# CH32V203_Wireless_Charge_V1_1.net
KiCad netlist of a schematic drawn in EasyEDA Pro
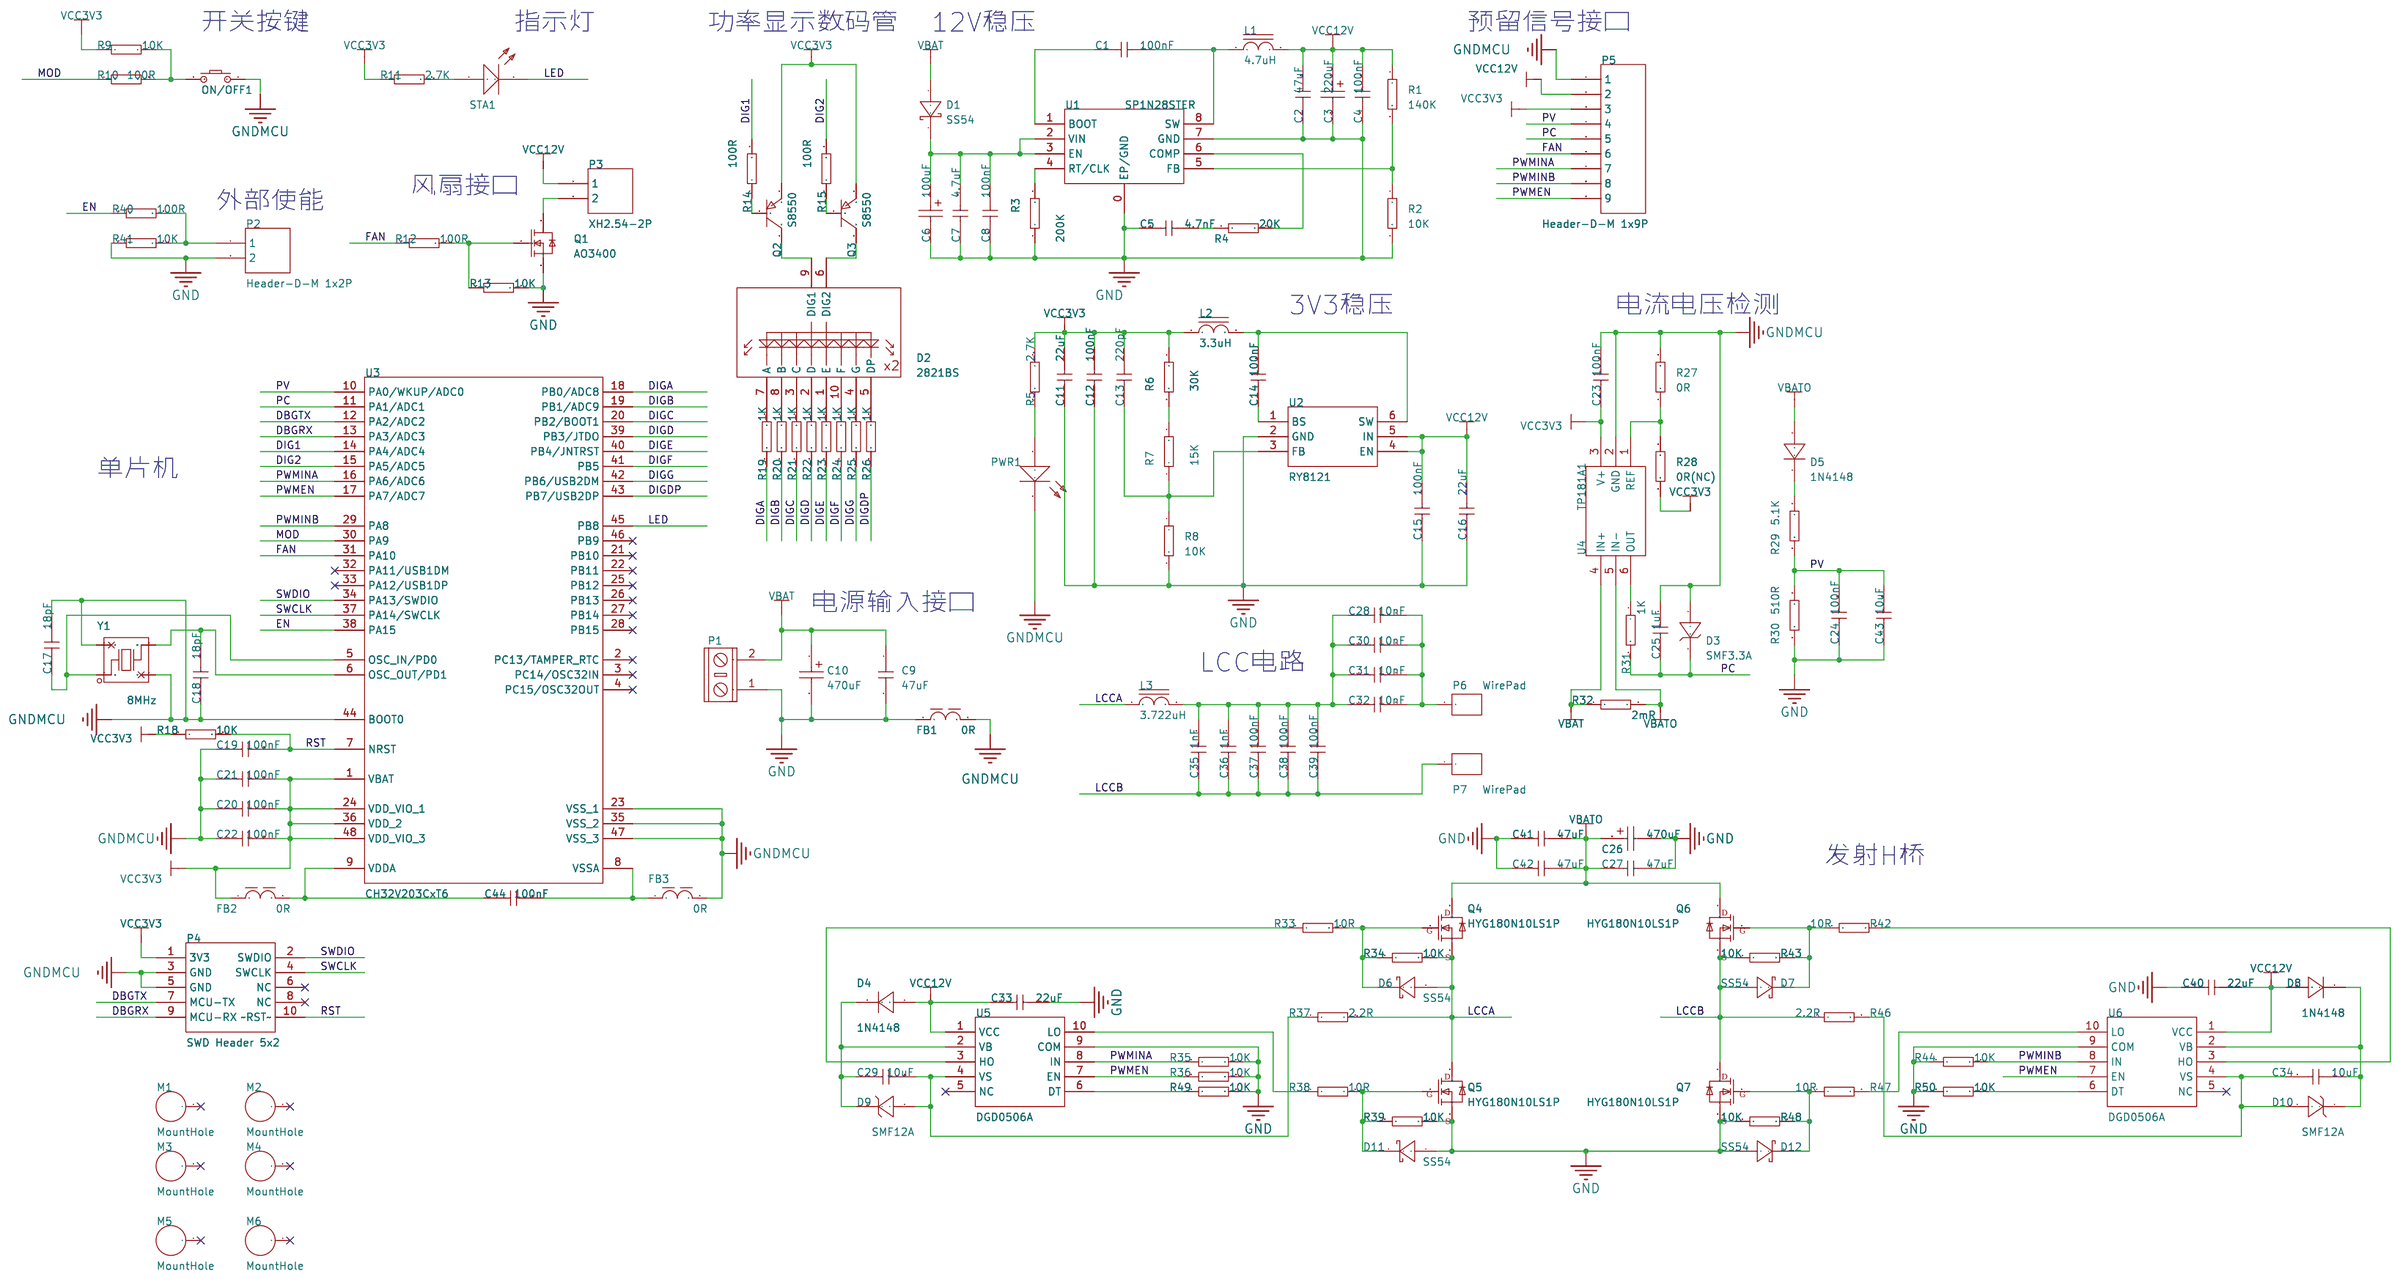
[diagram p0: schematic sheet]

(export (version "E")
  (design (tool "Eeschema 10.0.6"))
  (components
    (comp (ref "C1")
      (value "100nF")
      (footprint "easyedapro:CAPC1608[0603]S-N")
      (libsource (lib "easyedapro") (part "100nF 0603 50V X7R"))
    )
    (comp (ref "C2")
      (value "47uF")
      (footprint "easyedapro:CAPC3216[1206]S")
      (libsource (lib "easyedapro") (part "47uF 1206 25V X5R"))
    )
    (comp (ref "C3")
      (value "220uF")
      (footprint "easyedapro:Cap-S-D 2.5-6.3X8")
      (libsource (lib "easyedapro") (part "S-D 220uF 25V 6.3x8"))
    )
    (comp (ref "C4")
      (value "100nF")
      (footprint "easyedapro:CAPC1608[0603]S-N")
      (libsource (lib "easyedapro") (part "100nF 0603 50V X7R"))
    )
    (comp (ref "C5")
      (value "4.7nF")
      (footprint "easyedapro:CAPC1608[0603]S-N")
      (libsource (lib "easyedapro") (part "4.7nF 0603 50V X7R"))
    )
    (comp (ref "C6")
      (value "100uF")
      (footprint "easyedapro:Cap-S-D 2.5-6.3X8")
      (libsource (lib "easyedapro") (part "S-D 100uF 35V 6.3x8"))
    )
    (comp (ref "C7")
      (value "4.7uF")
      (footprint "easyedapro:CAPC3216[1206]S")
      (libsource (lib "easyedapro") (part "4.7uF 1206 35V X5R"))
    )
    (comp (ref "C8")
      (value "100nF")
      (footprint "easyedapro:CAPC1608[0603]S-N")
      (libsource (lib "easyedapro") (part "100nF 0603 50V X7R"))
    )
    (comp (ref "C9")
      (value "47uF")
      (footprint "easyedapro:CAPC4532[1812]S")
      (libsource (lib "easyedapro") (part "47uF 1812 50V X5R"))
    )
    (comp (ref "C10")
      (value "470uF")
      (footprint "easyedapro:Cap-S-D 3.5-8x14")
      (libsource (lib "easyedapro") (part "S-D 470uF 35V 8x14"))
    )
    (comp (ref "C11")
      (value "22uF")
      (footprint "easyedapro:CAPC2012[0805]S-N")
      (libsource (lib "easyedapro") (part "22uF 0805 25V X5R"))
    )
    (comp (ref "C12")
      (value "100nF")
      (footprint "easyedapro:CAPC1608[0603]S-N")
      (libsource (lib "easyedapro") (part "100nF 0603 50V X7R"))
    )
    (comp (ref "C13")
      (value "220pF")
      (footprint "easyedapro:CAPC1608[0603]S-N")
      (libsource (lib "easyedapro") (part "220pF 0603 50V X7R"))
    )
    (comp (ref "C14")
      (value "100nF")
      (footprint "easyedapro:CAPC1608[0603]S-N")
      (libsource (lib "easyedapro") (part "100nF 0603 50V X7R"))
    )
    (comp (ref "C15")
      (value "100nF")
      (footprint "easyedapro:CAPC1608[0603]S-N")
      (libsource (lib "easyedapro") (part "100nF 0603 50V X7R"))
    )
    (comp (ref "C16")
      (value "22uF")
      (footprint "easyedapro:CAPC2012[0805]S-N")
      (libsource (lib "easyedapro") (part "22uF 0805 25V X5R"))
    )
    (comp (ref "C17")
      (value "18pF")
      (footprint "easyedapro:CAPC1608[0603]S-N")
      (libsource (lib "easyedapro") (part "18pF 0603 50V COG"))
    )
    (comp (ref "C18")
      (value "18pF")
      (footprint "easyedapro:CAPC1608[0603]S-N")
      (libsource (lib "easyedapro") (part "18pF 0603 50V COG"))
    )
    (comp (ref "C19")
      (value "100nF")
      (footprint "easyedapro:CAPC1608[0603]S-N")
      (libsource (lib "easyedapro") (part "100nF 0603 50V X7R"))
    )
    (comp (ref "C20")
      (value "100nF")
      (footprint "easyedapro:CAPC1608[0603]S-N")
      (libsource (lib "easyedapro") (part "100nF 0603 50V X7R"))
    )
    (comp (ref "C21")
      (value "100nF")
      (footprint "easyedapro:CAPC1608[0603]S-N")
      (libsource (lib "easyedapro") (part "100nF 0603 50V X7R"))
    )
    (comp (ref "C22")
      (value "100nF")
      (footprint "easyedapro:CAPC1608[0603]S-N")
      (libsource (lib "easyedapro") (part "100nF 0603 50V X7R"))
    )
    (comp (ref "C23")
      (value "100nF")
      (footprint "easyedapro:CAPC1608[0603]S-N")
      (libsource (lib "easyedapro") (part "100nF 0603 50V X7R"))
    )
    (comp (ref "C24")
      (value "100nF")
      (footprint "easyedapro:CAPC1608[0603]S-N")
      (libsource (lib "easyedapro") (part "100nF 0603 50V X7R"))
    )
    (comp (ref "C25")
      (value "1uF")
      (footprint "easyedapro:CAPC1608[0603]S-N")
      (libsource (lib "easyedapro") (part "1uF 0603 16V X7R"))
    )
    (comp (ref "C26")
      (value "470uF")
      (footprint "easyedapro:Cap-S-D 3.5-8x14")
      (libsource (lib "easyedapro") (part "S-D 470uF 35V 8x14"))
    )
    (comp (ref "C27")
      (value "47uF")
      (footprint "easyedapro:CAPC4532[1812]S")
      (libsource (lib "easyedapro") (part "47uF 1812 50V X5R"))
    )
    (comp (ref "C28")
      (value "10nF")
      (footprint "easyedapro:CAPC3216[1206]S")
      (libsource (lib "easyedapro") (part "10nF 1206 100V C0G"))
    )
    (comp (ref "C29")
      (value "10uF")
      (footprint "easyedapro:CAPC2012[0805]S-N")
      (libsource (lib "easyedapro") (part "10uF 0805 25V X5R"))
    )
    (comp (ref "C30")
      (value "10nF")
      (footprint "easyedapro:CAPC3216[1206]S")
      (libsource (lib "easyedapro") (part "10nF 1206 100V C0G"))
    )
    (comp (ref "C31")
      (value "10nF")
      (footprint "easyedapro:CAPC3216[1206]S")
      (libsource (lib "easyedapro") (part "10nF 1206 100V C0G"))
    )
    (comp (ref "C32")
      (value "10nF")
      (footprint "easyedapro:CAPC3216[1206]S")
      (libsource (lib "easyedapro") (part "10nF 1206 100V C0G"))
    )
    (comp (ref "C33")
      (value "22uF")
      (footprint "easyedapro:CAPC2012[0805]S-N")
      (libsource (lib "easyedapro") (part "22uF 0805 25V X5R"))
    )
    (comp (ref "C34")
      (value "10uF")
      (footprint "easyedapro:CAPC2012[0805]S-N")
      (libsource (lib "easyedapro") (part "10uF 0805 25V X5R"))
    )
    (comp (ref "C35")
      (value "1nF")
      (footprint "easyedapro:CAPC3216[1206]S")
      (libsource (lib "easyedapro") (part "1nF 1206 100V C0G"))
    )
    (comp (ref "C36")
      (value "1nF")
      (footprint "easyedapro:CAPC3216[1206]S")
      (libsource (lib "easyedapro") (part "1nF 1206 100V C0G"))
    )
    (comp (ref "C37")
      (value "100nF")
      (footprint "easyedapro:CAPC3216[1206]S")
      (libsource (lib "easyedapro") (part "100nF 1206 100V C0G"))
    )
    (comp (ref "C38")
      (value "100nF")
      (footprint "easyedapro:CAPC3216[1206]S")
      (libsource (lib "easyedapro") (part "100nF 1206 100V C0G"))
    )
    (comp (ref "C39")
      (value "100nF")
      (footprint "easyedapro:CAPC3216[1206]S")
      (libsource (lib "easyedapro") (part "100nF 1206 100V C0G"))
    )
    (comp (ref "C40")
      (value "22uF")
      (footprint "easyedapro:CAPC2012[0805]S-N")
      (libsource (lib "easyedapro") (part "22uF 0805 25V X5R"))
    )
    (comp (ref "C41")
      (value "47uF")
      (footprint "easyedapro:CAPC4532[1812]S")
      (libsource (lib "easyedapro") (part "47uF 1812 50V X5R"))
    )
    (comp (ref "C42")
      (value "47uF")
      (footprint "easyedapro:CAPC4532[1812]S")
      (libsource (lib "easyedapro") (part "47uF 1812 50V X5R"))
    )
    (comp (ref "C43")
      (value "10uF")
      (footprint "easyedapro:CAPC2012[0805]S-N")
      (libsource (lib "easyedapro") (part "10uF 0805 25V X5R"))
    )
    (comp (ref "C44")
      (value "100nF")
      (footprint "easyedapro:CAPC1608[0603]S-N")
      (libsource (lib "easyedapro") (part "100nF 0603 50V X7R"))
    )
    (comp (ref "D1")
      (value "SS54")
      (footprint "easyedapro:SMA-L[DO-214AC]")
      (libsource (lib "easyedapro") (part "SS54"))
    )
    (comp (ref "D2")
      (value "2821BS")
      (footprint "easyedapro:2821AS/BS")
      (libsource (lib "easyedapro") (part "2821BS"))
    )
    (comp (ref "D3")
      (value "SMF3.3A")
      (footprint "easyedapro:SOD-123-L")
      (libsource (lib "easyedapro") (part "Diode TVS Uni-Dir_1"))
    )
    (comp (ref "D4")
      (value "1N4148")
      (footprint "easyedapro:SOD-123-L")
      (libsource (lib "easyedapro") (part "Diode"))
    )
    (comp (ref "D5")
      (value "1N4148")
      (footprint "easyedapro:SOD-123-L")
      (libsource (lib "easyedapro") (part "Diode"))
    )
    (comp (ref "D6")
      (value "SS54")
      (footprint "easyedapro:SMA-L[DO-214AC]")
      (libsource (lib "easyedapro") (part "SS54"))
    )
    (comp (ref "D7")
      (value "SS54")
      (footprint "easyedapro:SMA-L[DO-214AC]")
      (libsource (lib "easyedapro") (part "SS54"))
    )
    (comp (ref "D8")
      (value "1N4148")
      (footprint "easyedapro:SOD-123-L")
      (libsource (lib "easyedapro") (part "Diode"))
    )
    (comp (ref "D9")
      (value "SMF12A")
      (footprint "easyedapro:SOD-123-L")
      (libsource (lib "easyedapro") (part "Diode TVS Uni-Dir"))
    )
    (comp (ref "D10")
      (value "SMF12A")
      (footprint "easyedapro:SOD-123-L")
      (libsource (lib "easyedapro") (part "Diode TVS Uni-Dir"))
    )
    (comp (ref "D11")
      (value "SS54")
      (footprint "easyedapro:SMA-L[DO-214AC]")
      (libsource (lib "easyedapro") (part "SS54"))
    )
    (comp (ref "D12")
      (value "SS54")
      (footprint "easyedapro:SMA-L[DO-214AC]")
      (libsource (lib "easyedapro") (part "SS54"))
    )
    (comp (ref "FB1")
      (value "0R")
      (footprint "easyedapro:INDC1608[0603]S")
      (libsource (lib "easyedapro") (part "FB-Chip"))
    )
    (comp (ref "FB2")
      (value "0R")
      (footprint "easyedapro:INDC1608[0603]S")
      (libsource (lib "easyedapro") (part "FB-Chip"))
    )
    (comp (ref "FB3")
      (value "0R")
      (footprint "easyedapro:INDC1608[0603]S")
      (libsource (lib "easyedapro") (part "FB-Chip"))
    )
    (comp (ref "L1")
      (value "4.7uH")
      (footprint "easyedapro:0630 TPC 7*7*3")
      (libsource (lib "easyedapro") (part "Ind-Power"))
    )
    (comp (ref "L2")
      (value "3.3uH")
      (footprint "easyedapro:0402 TPC 4*4*2")
      (libsource (lib "easyedapro") (part "Ind-Power_1"))
    )
    (comp (ref "L3")
      (value "3.722uH")
      (footprint "easyedapro:T94/106-LAY")
      (libsource (lib "easyedapro") (part "Ind-Power_2"))
    )
    (comp (ref "M1")
      (value "MountHole")
      (footprint "easyedapro:M3-MountHole-Plated")
      (libsource (lib "easyedapro") (part "MountHole"))
    )
    (comp (ref "M2")
      (value "MountHole")
      (footprint "easyedapro:M3-MountHole-Plated")
      (libsource (lib "easyedapro") (part "MountHole"))
    )
    (comp (ref "M3")
      (value "MountHole")
      (footprint "easyedapro:M3-MountHole-Plated")
      (libsource (lib "easyedapro") (part "MountHole"))
    )
    (comp (ref "M4")
      (value "MountHole")
      (footprint "easyedapro:M3-MountHole-Plated")
      (libsource (lib "easyedapro") (part "MountHole"))
    )
    (comp (ref "M5")
      (value "MountHole")
      (footprint "easyedapro:M3-MountHole-Plated")
      (libsource (lib "easyedapro") (part "MountHole"))
    )
    (comp (ref "M6")
      (value "MountHole")
      (footprint "easyedapro:M3-MountHole-Plated")
      (libsource (lib "easyedapro") (part "MountHole"))
    )
    (comp (ref "ON/OFF1")
      (value "Button")
      (footprint "easyedapro:KEY-2-DIP-6*6-S")
      (libsource (lib "easyedapro") (part "KEY"))
    )
    (comp (ref "P1")
      (value "KF/WJ/DG 30x connecter")
      (footprint "easyedapro:KF/WJ/DG 301-2p-5.0mm")
      (libsource (lib "easyedapro") (part "KF/WJ/DG 30x"))
    )
    (comp (ref "P2")
      (value "Header-D-M 1x2P")
      (footprint "easyedapro:HDR1X2-M")
      (libsource (lib "easyedapro") (part "Header-D-M 1x2P"))
    )
    (comp (ref "P3")
      (value "XH2.54-2P")
      (footprint "easyedapro:XH2.54-2P-DV")
      (libsource (lib "easyedapro") (part "XH2.54-2P"))
    )
    (comp (ref "P4")
      (value "SWD Header 5x2")
      (footprint "easyedapro:HDR2X5-M")
      (libsource (lib "easyedapro") (part "SWD Header 5x2"))
    )
    (comp (ref "P5")
      (value "Header-D-M 1x9P")
      (footprint "easyedapro:HDR1X9-M")
      (libsource (lib "easyedapro") (part "Header-D-M 1x9P"))
    )
    (comp (ref "P6")
      (value "WirePad")
      (footprint "easyedapro:WirePad-4x6")
      (libsource (lib "easyedapro") (part "WirePad"))
    )
    (comp (ref "P7")
      (value "WirePad")
      (footprint "easyedapro:WirePad-4x6")
      (libsource (lib "easyedapro") (part "WirePad"))
    )
    (comp (ref "PWR1")
      (value "LED 3R")
      (footprint "easyedapro:LED-R3-H5-SINGLE-R")
      (libsource (lib "easyedapro") (part "LED DIP Red"))
    )
    (comp (ref "Q1")
      (value "AO3400")
      (footprint "easyedapro:SOT-23")
      (libsource (lib "easyedapro") (part "AO3400"))
    )
    (comp (ref "Q2")
      (value "S8550")
      (footprint "easyedapro:SOT-23")
      (libsource (lib "easyedapro") (part "PNP S8550"))
    )
    (comp (ref "Q3")
      (value "S8550")
      (footprint "easyedapro:SOT-23")
      (libsource (lib "easyedapro") (part "PNP S8550"))
    )
    (comp (ref "Q4")
      (value "HYG180N10LS1P")
      (footprint "easyedapro:TO-220-LAY")
      (libsource (lib "easyedapro") (part "HYG180N10LS1P"))
    )
    (comp (ref "Q5")
      (value "HYG180N10LS1P")
      (footprint "easyedapro:TO-220-LAY")
      (libsource (lib "easyedapro") (part "HYG180N10LS1P"))
    )
    (comp (ref "Q6")
      (value "HYG180N10LS1P")
      (footprint "easyedapro:TO-220-LAY")
      (libsource (lib "easyedapro") (part "HYG180N10LS1P"))
    )
    (comp (ref "Q7")
      (value "HYG180N10LS1P")
      (footprint "easyedapro:TO-220-LAY")
      (libsource (lib "easyedapro") (part "HYG180N10LS1P"))
    )
    (comp (ref "R1")
      (value "140K")
      (footprint "easyedapro:RESC1608[0603]S-N")
      (libsource (lib "easyedapro") (part "Res-Chip_6"))
    )
    (comp (ref "R2")
      (value "10K")
      (footprint "easyedapro:RESC1608[0603]S-N")
      (libsource (lib "easyedapro") (part "Res-Chip"))
    )
    (comp (ref "R3")
      (value "200K")
      (footprint "easyedapro:RESC1608[0603]S-N")
      (libsource (lib "easyedapro") (part "Res-Chip_4"))
    )
    (comp (ref "R4")
      (value "20K")
      (footprint "easyedapro:RESC1608[0603]S-N")
      (libsource (lib "easyedapro") (part "Res-Chip_5"))
    )
    (comp (ref "R5")
      (value "2.7K")
      (footprint "easyedapro:RESC1608[0603]S-N")
      (libsource (lib "easyedapro") (part "Res-Chip_3"))
    )
    (comp (ref "R6")
      (value "30K")
      (footprint "easyedapro:RESC1608[0603]S-N")
      (libsource (lib "easyedapro") (part "Res-Chip_8"))
    )
    (comp (ref "R7")
      (value "15K")
      (footprint "easyedapro:RESC1608[0603]S-N")
      (libsource (lib "easyedapro") (part "Res-Chip_7"))
    )
    (comp (ref "R8")
      (value "10K")
      (footprint "easyedapro:RESC1608[0603]S-N")
      (libsource (lib "easyedapro") (part "Res-Chip"))
    )
    (comp (ref "R9")
      (value "10K")
      (footprint "easyedapro:RESC1608[0603]S-N")
      (libsource (lib "easyedapro") (part "Res-Chip"))
    )
    (comp (ref "R10")
      (value "100R")
      (footprint "easyedapro:RESC1608[0603]S-N")
      (libsource (lib "easyedapro") (part "Res-Chip_1"))
    )
    (comp (ref "R11")
      (value "2.7K")
      (footprint "easyedapro:RESC1608[0603]S-N")
      (libsource (lib "easyedapro") (part "Res-Chip_3"))
    )
    (comp (ref "R12")
      (value "100R")
      (footprint "easyedapro:RESC1608[0603]S-N")
      (libsource (lib "easyedapro") (part "Res-Chip_1"))
    )
    (comp (ref "R13")
      (value "10K")
      (footprint "easyedapro:RESC1608[0603]S-N")
      (libsource (lib "easyedapro") (part "Res-Chip"))
    )
    (comp (ref "R14")
      (value "100R")
      (footprint "easyedapro:RESC1608[0603]S-N")
      (libsource (lib "easyedapro") (part "Res-Chip_1"))
    )
    (comp (ref "R15")
      (value "100R")
      (footprint "easyedapro:RESC1608[0603]S-N")
      (libsource (lib "easyedapro") (part "Res-Chip_1"))
    )
    (comp (ref "R18")
      (value "10K")
      (footprint "easyedapro:RESC1608[0603]S-N")
      (libsource (lib "easyedapro") (part "Res-Chip"))
    )
    (comp (ref "R19")
      (value "1K")
      (footprint "easyedapro:RESC1608[0603]S-N")
      (libsource (lib "easyedapro") (part "Res-Chip_2"))
    )
    (comp (ref "R20")
      (value "1K")
      (footprint "easyedapro:RESC1608[0603]S-N")
      (libsource (lib "easyedapro") (part "Res-Chip_2"))
    )
    (comp (ref "R21")
      (value "1K")
      (footprint "easyedapro:RESC1608[0603]S-N")
      (libsource (lib "easyedapro") (part "Res-Chip_2"))
    )
    (comp (ref "R22")
      (value "1K")
      (footprint "easyedapro:RESC1608[0603]S-N")
      (libsource (lib "easyedapro") (part "Res-Chip_2"))
    )
    (comp (ref "R23")
      (value "1K")
      (footprint "easyedapro:RESC1608[0603]S-N")
      (libsource (lib "easyedapro") (part "Res-Chip_2"))
    )
    (comp (ref "R24")
      (value "1K")
      (footprint "easyedapro:RESC1608[0603]S-N")
      (libsource (lib "easyedapro") (part "Res-Chip_2"))
    )
    (comp (ref "R25")
      (value "1K")
      (footprint "easyedapro:RESC1608[0603]S-N")
      (libsource (lib "easyedapro") (part "Res-Chip_2"))
    )
    (comp (ref "R26")
      (value "1K")
      (footprint "easyedapro:RESC1608[0603]S-N")
      (libsource (lib "easyedapro") (part "Res-Chip_2"))
    )
    (comp (ref "R27")
      (value "0R")
      (footprint "easyedapro:RESC1608[0603]S-N")
      (libsource (lib "easyedapro") (part "Res-Chip_12"))
    )
    (comp (ref "R28")
      (value "0R(NC)")
      (footprint "easyedapro:RESC1608[0603]S-N")
      (libsource (lib "easyedapro") (part "Res-Chip_11"))
    )
    (comp (ref "R29")
      (value "5.1K")
      (footprint "easyedapro:RESC1608[0603]S-N")
      (libsource (lib "easyedapro") (part "Res-Chip_14"))
    )
    (comp (ref "R30")
      (value "510R")
      (footprint "easyedapro:RESC1608[0603]S-N")
      (libsource (lib "easyedapro") (part "Res-Chip_15"))
    )
    (comp (ref "R31")
      (value "1K")
      (footprint "easyedapro:RESC1608[0603]S-N")
      (libsource (lib "easyedapro") (part "Res-Chip_2"))
    )
    (comp (ref "R32")
      (value "2mR")
      (footprint "easyedapro:RESC6332[2512]S")
      (libsource (lib "easyedapro") (part "Res-Chip_10"))
    )
    (comp (ref "R33")
      (value "10R")
      (footprint "easyedapro:RESC2012[0805]S-N")
      (libsource (lib "easyedapro") (part "Res-Chip_9"))
    )
    (comp (ref "R34")
      (value "10K")
      (footprint "easyedapro:RESC1608[0603]S-N")
      (libsource (lib "easyedapro") (part "Res-Chip"))
    )
    (comp (ref "R35")
      (value "10K")
      (footprint "easyedapro:RESC1608[0603]S-N")
      (libsource (lib "easyedapro") (part "Res-Chip"))
    )
    (comp (ref "R36")
      (value "10K")
      (footprint "easyedapro:RESC1608[0603]S-N")
      (libsource (lib "easyedapro") (part "Res-Chip"))
    )
    (comp (ref "R37")
      (value "2.2R")
      (footprint "easyedapro:RESC2012[0805]S-N")
      (libsource (lib "easyedapro") (part "Res-Chip_13"))
    )
    (comp (ref "R38")
      (value "10R")
      (footprint "easyedapro:RESC2012[0805]S-N")
      (libsource (lib "easyedapro") (part "Res-Chip_9"))
    )
    (comp (ref "R39")
      (value "10K")
      (footprint "easyedapro:RESC1608[0603]S-N")
      (libsource (lib "easyedapro") (part "Res-Chip"))
    )
    (comp (ref "R40")
      (value "100R")
      (footprint "easyedapro:RESC1608[0603]S-N")
      (libsource (lib "easyedapro") (part "Res-Chip_1"))
    )
    (comp (ref "R41")
      (value "10K")
      (footprint "easyedapro:RESC1608[0603]S-N")
      (libsource (lib "easyedapro") (part "Res-Chip"))
    )
    (comp (ref "R42")
      (value "10R")
      (footprint "easyedapro:RESC2012[0805]S-N")
      (libsource (lib "easyedapro") (part "Res-Chip_9"))
    )
    (comp (ref "R43")
      (value "10K")
      (footprint "easyedapro:RESC1608[0603]S-N")
      (libsource (lib "easyedapro") (part "Res-Chip"))
    )
    (comp (ref "R44")
      (value "10K")
      (footprint "easyedapro:RESC1608[0603]S-N")
      (libsource (lib "easyedapro") (part "Res-Chip"))
    )
    (comp (ref "R46")
      (value "2.2R")
      (footprint "easyedapro:RESC2012[0805]S-N")
      (libsource (lib "easyedapro") (part "Res-Chip_13"))
    )
    (comp (ref "R47")
      (value "10R")
      (footprint "easyedapro:RESC2012[0805]S-N")
      (libsource (lib "easyedapro") (part "Res-Chip_9"))
    )
    (comp (ref "R48")
      (value "10K")
      (footprint "easyedapro:RESC1608[0603]S-N")
      (libsource (lib "easyedapro") (part "Res-Chip"))
    )
    (comp (ref "R49")
      (value "10K")
      (footprint "easyedapro:RESC1608[0603]S-N")
      (libsource (lib "easyedapro") (part "Res-Chip"))
    )
    (comp (ref "R50")
      (value "10K")
      (footprint "easyedapro:RESC1608[0603]S-N")
      (libsource (lib "easyedapro") (part "Res-Chip"))
    )
    (comp (ref "STA1")
      (value "LED")
      (footprint "easyedapro:LED-R3-H5-SINGLE-B")
      (libsource (lib "easyedapro") (part "LED DIP Blue"))
    )
    (comp (ref "U1")
      (value "SP1N28STER")
      (footprint "easyedapro:SOP-8E")
      (libsource (lib "easyedapro") (part "SP1N28STER"))
    )
    (comp (ref "U2")
      (value "RY8121")
      (footprint "easyedapro:SOT-23-6")
      (libsource (lib "easyedapro") (part "RY8121"))
    )
    (comp (ref "U3")
      (value "CH32V203CxT6")
      (footprint "easyedapro:LQFP48_L")
      (libsource (lib "easyedapro") (part "CH32V203CxT6"))
    )
    (comp (ref "U4")
      (value "TP181A1")
      (footprint "easyedapro:SOT-363")
      (libsource (lib "easyedapro") (part "TP181Ax"))
    )
    (comp (ref "U5")
      (value "DGD0506A")
      (footprint "easyedapro:MSOP-10")
      (libsource (lib "easyedapro") (part "DGD0506A"))
    )
    (comp (ref "U6")
      (value "DGD0506A")
      (footprint "easyedapro:MSOP-10")
      (libsource (lib "easyedapro") (part "DGD0506A"))
    )
    (comp (ref "Y1")
      (value "8MHz")
      (footprint "easyedapro:X3225-4")
      (libsource (lib "easyedapro") (part "XTAL-4"))
    )
  )
  (nets
    (net (code "1") (name "/DBGRX") (class "Default")
      (node (ref "P4") (pin "9") (pinfunction "MCU-RX_9") (pintype "input"))
      (node (ref "U3") (pin "13") (pinfunction "PA3/ADC3_13") (pintype "input"))
    )
    (net (code "2") (name "/DBGTX") (class "Default")
      (node (ref "P4") (pin "7") (pinfunction "MCU-TX_7") (pintype "input"))
      (node (ref "U3") (pin "12") (pinfunction "PA2/ADC2_12") (pintype "input"))
    )
    (net (code "3") (name "/DIG1") (class "Default")
      (node (ref "R14") (pin "2") (pinfunction "2_2") (pintype "input"))
      (node (ref "U3") (pin "14") (pinfunction "PA4/ADC4_14") (pintype "input"))
    )
    (net (code "4") (name "/DIG2") (class "Default")
      (node (ref "R15") (pin "2") (pinfunction "2_2") (pintype "input"))
      (node (ref "U3") (pin "15") (pinfunction "PA5/ADC5_15") (pintype "input"))
    )
    (net (code "5") (name "/DIGA") (class "Default")
      (node (ref "R19") (pin "1") (pinfunction "1_1") (pintype "input"))
      (node (ref "U3") (pin "18") (pinfunction "PB0/ADC8_18") (pintype "input"))
    )
    (net (code "6") (name "/DIGB") (class "Default")
      (node (ref "R20") (pin "1") (pinfunction "1_1") (pintype "input"))
      (node (ref "U3") (pin "19") (pinfunction "PB1/ADC9_19") (pintype "input"))
    )
    (net (code "7") (name "/DIGC") (class "Default")
      (node (ref "R21") (pin "1") (pinfunction "1_1") (pintype "input"))
      (node (ref "U3") (pin "20") (pinfunction "PB2/BOOT1_20") (pintype "input"))
    )
    (net (code "8") (name "/DIGD") (class "Default")
      (node (ref "R22") (pin "1") (pinfunction "1_1") (pintype "input"))
      (node (ref "U3") (pin "39") (pinfunction "PB3/JTDO_39") (pintype "input"))
    )
    (net (code "9") (name "/DIGDP") (class "Default")
      (node (ref "R26") (pin "1") (pinfunction "1_1") (pintype "input"))
      (node (ref "U3") (pin "43") (pinfunction "PB7/USB2DP_43") (pintype "input"))
    )
    (net (code "10") (name "/DIGE") (class "Default")
      (node (ref "R23") (pin "1") (pinfunction "1_1") (pintype "input"))
      (node (ref "U3") (pin "40") (pinfunction "PB4/JNTRST_40") (pintype "input"))
    )
    (net (code "11") (name "/DIGF") (class "Default")
      (node (ref "R24") (pin "1") (pinfunction "1_1") (pintype "input"))
      (node (ref "U3") (pin "41") (pinfunction "PB5_41") (pintype "input"))
    )
    (net (code "12") (name "/DIGG") (class "Default")
      (node (ref "R25") (pin "1") (pinfunction "1_1") (pintype "input"))
      (node (ref "U3") (pin "42") (pinfunction "PB6/USB2DM_42") (pintype "input"))
    )
    (net (code "13") (name "/EN") (class "Default")
      (node (ref "R40") (pin "1") (pinfunction "1_1") (pintype "input"))
      (node (ref "U3") (pin "38") (pinfunction "PA15_38") (pintype "input"))
    )
    (net (code "14") (name "/FAN") (class "Default")
      (node (ref "P5") (pin "6") (pinfunction "6_6") (pintype "input"))
      (node (ref "R12") (pin "1") (pinfunction "1_1") (pintype "input"))
      (node (ref "U3") (pin "31") (pinfunction "PA10_31") (pintype "input"))
    )
    (net (code "15") (name "/LCCA") (class "Default")
      (node (ref "D6") (pin "A") (pinfunction "A_A") (pintype "input"))
      (node (ref "L3") (pin "1") (pinfunction "1_1") (pintype "input"))
      (node (ref "Q4") (pin "3") (pinfunction "S_3") (pintype "input"))
      (node (ref "Q5") (pin "2") (pinfunction "D_2") (pintype "input"))
      (node (ref "R34") (pin "2") (pinfunction "2_2") (pintype "input"))
      (node (ref "R37") (pin "2") (pinfunction "2_2") (pintype "input"))
    )
    (net (code "16") (name "/LCCB") (class "Default")
      (node (ref "C35") (pin "1") (pinfunction "1_1") (pintype "input"))
      (node (ref "C36") (pin "1") (pinfunction "1_1") (pintype "input"))
      (node (ref "C37") (pin "1") (pinfunction "1_1") (pintype "input"))
      (node (ref "C38") (pin "1") (pinfunction "1_1") (pintype "input"))
      (node (ref "C39") (pin "1") (pinfunction "1_1") (pintype "input"))
      (node (ref "D7") (pin "A") (pinfunction "A_A") (pintype "input"))
      (node (ref "P7") (pin "1") (pinfunction "1_1") (pintype "input"))
      (node (ref "Q6") (pin "3") (pinfunction "S_3") (pintype "input"))
      (node (ref "Q7") (pin "2") (pinfunction "D_2") (pintype "input"))
      (node (ref "R43") (pin "1") (pinfunction "1_1") (pintype "input"))
      (node (ref "R46") (pin "1") (pinfunction "1_1") (pintype "input"))
    )
    (net (code "17") (name "/LED") (class "Default")
      (node (ref "STA1") (pin "2") (pinfunction "K_2") (pintype "input"))
      (node (ref "U3") (pin "45") (pinfunction "PB8_45") (pintype "input"))
    )
    (net (code "18") (name "/MOD") (class "Default")
      (node (ref "R10") (pin "1") (pinfunction "1_1") (pintype "input"))
      (node (ref "U3") (pin "30") (pinfunction "PA9_30") (pintype "input"))
    )
    (net (code "19") (name "/PC") (class "Default")
      (node (ref "C25") (pin "1") (pinfunction "1_1") (pintype "input"))
      (node (ref "D3") (pin "K") (pinfunction "K_K") (pintype "input"))
      (node (ref "P5") (pin "5") (pinfunction "5_5") (pintype "input"))
      (node (ref "R31") (pin "2") (pinfunction "2_2") (pintype "input"))
      (node (ref "U3") (pin "11") (pinfunction "PA1/ADC1_11") (pintype "input"))
    )
    (net (code "20") (name "/PV") (class "Default")
      (node (ref "C24") (pin "1") (pinfunction "1_1") (pintype "input"))
      (node (ref "C43") (pin "1") (pinfunction "1_1") (pintype "input"))
      (node (ref "P5") (pin "4") (pinfunction "4_4") (pintype "input"))
      (node (ref "R29") (pin "2") (pinfunction "2_2") (pintype "input"))
      (node (ref "R30") (pin "1") (pinfunction "1_1") (pintype "input"))
      (node (ref "U3") (pin "10") (pinfunction "PA0/WKUP/ADC0_10") (pintype "input"))
    )
    (net (code "21") (name "/PWMEN") (class "Default")
      (node (ref "P5") (pin "9") (pinfunction "9_9") (pintype "input"))
      (node (ref "R36") (pin "1") (pinfunction "1_1") (pintype "input"))
      (node (ref "U3") (pin "17") (pinfunction "PA7/ADC7_17") (pintype "input"))
      (node (ref "U5") (pin "7") (pinfunction "EN_7") (pintype "input"))
      (node (ref "U6") (pin "7") (pinfunction "EN_7") (pintype "input"))
    )
    (net (code "22") (name "/PWMINA") (class "Default")
      (node (ref "P5") (pin "7") (pinfunction "7_7") (pintype "input"))
      (node (ref "R35") (pin "1") (pinfunction "1_1") (pintype "input"))
      (node (ref "U3") (pin "16") (pinfunction "PA6/ADC6_16") (pintype "input"))
      (node (ref "U5") (pin "8") (pinfunction "IN_8") (pintype "input"))
    )
    (net (code "23") (name "/PWMINB") (class "Default")
      (node (ref "P5") (pin "8") (pinfunction "8_8") (pintype "input"))
      (node (ref "R44") (pin "2") (pinfunction "2_2") (pintype "input"))
      (node (ref "U3") (pin "29") (pinfunction "PA8_29") (pintype "input"))
      (node (ref "U6") (pin "8") (pinfunction "IN_8") (pintype "input"))
    )
    (net (code "24") (name "/RST") (class "Default")
      (node (ref "C19") (pin "2") (pinfunction "2_2") (pintype "input"))
      (node (ref "P4") (pin "10") (pinfunction "~RST~_10") (pintype "input"))
      (node (ref "R18") (pin "2") (pinfunction "2_2") (pintype "input"))
      (node (ref "U3") (pin "7") (pinfunction "NRST_7") (pintype "input"))
    )
    (net (code "25") (name "/SWCLK") (class "Default")
      (node (ref "P4") (pin "4") (pinfunction "SWCLK_4") (pintype "input"))
      (node (ref "U3") (pin "37") (pinfunction "PA14/SWCLK_37") (pintype "input"))
    )
    (net (code "26") (name "/SWDIO") (class "Default")
      (node (ref "P4") (pin "2") (pinfunction "SWDIO_2") (pintype "input"))
      (node (ref "U3") (pin "34") (pinfunction "PA13/SWDIO_34") (pintype "input"))
    )
    (net (code "27") (name "GND") (class "Default")
      (node (ref "C10") (pin "2") (pinfunction "2_2") (pintype "input"))
      (node (ref "C11") (pin "2") (pinfunction "2_2") (pintype "input"))
      (node (ref "C12") (pin "2") (pinfunction "2_2") (pintype "input"))
      (node (ref "C15") (pin "2") (pinfunction "2_2") (pintype "input"))
      (node (ref "C16") (pin "2") (pinfunction "2_2") (pintype "input"))
      (node (ref "C2") (pin "1") (pinfunction "1_1") (pintype "input"))
      (node (ref "C24") (pin "2") (pinfunction "2_2") (pintype "input"))
      (node (ref "C26") (pin "2") (pinfunction "2_2") (pintype "input"))
      (node (ref "C27") (pin "2") (pinfunction "2_2") (pintype "input"))
      (node (ref "C3") (pin "2") (pinfunction "2_2") (pintype "input"))
      (node (ref "C33") (pin "2") (pinfunction "2_2") (pintype "input"))
      (node (ref "C4") (pin "1") (pinfunction "1_1") (pintype "input"))
      (node (ref "C40") (pin "1") (pinfunction "1_1") (pintype "input"))
      (node (ref "C41") (pin "1") (pinfunction "1_1") (pintype "input"))
      (node (ref "C42") (pin "1") (pinfunction "1_1") (pintype "input"))
      (node (ref "C43") (pin "2") (pinfunction "2_2") (pintype "input"))
      (node (ref "C5") (pin "1") (pinfunction "1_1") (pintype "input"))
      (node (ref "C6") (pin "2") (pinfunction "2_2") (pintype "input"))
      (node (ref "C7") (pin "1") (pinfunction "1_1") (pintype "input"))
      (node (ref "C8") (pin "1") (pinfunction "1_1") (pintype "input"))
      (node (ref "C9") (pin "2") (pinfunction "2_2") (pintype "input"))
      (node (ref "D11") (pin "A") (pinfunction "A_A") (pintype "input"))
      (node (ref "D12") (pin "A") (pinfunction "A_A") (pintype "input"))
      (node (ref "FB1") (pin "1") (pinfunction "1_1") (pintype "input"))
      (node (ref "P1") (pin "1") (pinfunction "1_1") (pintype "input"))
      (node (ref "P2") (pin "2") (pinfunction "2_2") (pintype "input"))
      (node (ref "Q1") (pin "2") (pinfunction "S_2") (pintype "input"))
      (node (ref "Q5") (pin "3") (pinfunction "S_3") (pintype "input"))
      (node (ref "Q7") (pin "3") (pinfunction "S_3") (pintype "input"))
      (node (ref "R13") (pin "2") (pinfunction "2_2") (pintype "input"))
      (node (ref "R2") (pin "2") (pinfunction "2_2") (pintype "input"))
      (node (ref "R3") (pin "1") (pinfunction "1_1") (pintype "input"))
      (node (ref "R30") (pin "2") (pinfunction "2_2") (pintype "input"))
      (node (ref "R35") (pin "2") (pinfunction "2_2") (pintype "input"))
      (node (ref "R36") (pin "2") (pinfunction "2_2") (pintype "input"))
      (node (ref "R39") (pin "2") (pinfunction "2_2") (pintype "input"))
      (node (ref "R41") (pin "1") (pinfunction "1_1") (pintype "input"))
      (node (ref "R44") (pin "1") (pinfunction "1_1") (pintype "input"))
      (node (ref "R48") (pin "1") (pinfunction "1_1") (pintype "input"))
      (node (ref "R49") (pin "2") (pinfunction "2_2") (pintype "input"))
      (node (ref "R50") (pin "1") (pinfunction "1_1") (pintype "input"))
      (node (ref "R8") (pin "2") (pinfunction "2_2") (pintype "input"))
      (node (ref "U1") (pin "0") (pinfunction "EP/GND_0") (pintype "input"))
      (node (ref "U1") (pin "7") (pinfunction "GND_7") (pintype "input"))
      (node (ref "U2") (pin "2") (pinfunction "GND_2") (pintype "input"))
      (node (ref "U5") (pin "9") (pinfunction "COM_9") (pintype "input"))
      (node (ref "U6") (pin "9") (pinfunction "COM_9") (pintype "input"))
    )
    (net (code "28") (name "GNDMCU") (class "Default")
      (node (ref "C17") (pin "2") (pinfunction "2_2") (pintype "input"))
      (node (ref "C18") (pin "2") (pinfunction "2_2") (pintype "input"))
      (node (ref "C19") (pin "1") (pinfunction "1_1") (pintype "input"))
      (node (ref "C20") (pin "1") (pinfunction "1_1") (pintype "input"))
      (node (ref "C21") (pin "1") (pinfunction "1_1") (pintype "input"))
      (node (ref "C22") (pin "1") (pinfunction "1_1") (pintype "input"))
      (node (ref "C23") (pin "1") (pinfunction "1_1") (pintype "input"))
      (node (ref "C25") (pin "2") (pinfunction "2_2") (pintype "input"))
      (node (ref "D3") (pin "A") (pinfunction "A_A") (pintype "input"))
      (node (ref "FB1") (pin "2") (pinfunction "2_2") (pintype "input"))
      (node (ref "FB3") (pin "2") (pinfunction "2_2") (pintype "input"))
      (node (ref "ON/OFF1") (pin "1") (pinfunction "1_1") (pintype "input"))
      (node (ref "P4") (pin "3") (pinfunction "GND_3") (pintype "input"))
      (node (ref "P4") (pin "5") (pinfunction "GND_5") (pintype "input"))
      (node (ref "P5") (pin "1") (pinfunction "1_1") (pintype "input"))
      (node (ref "PWR1") (pin "2") (pinfunction "K_2") (pintype "input"))
      (node (ref "R27") (pin "2") (pinfunction "2_2") (pintype "input"))
      (node (ref "U3") (pin "23") (pinfunction "VSS_1_23") (pintype "input"))
      (node (ref "U3") (pin "35") (pinfunction "VSS_2_35") (pintype "input"))
      (node (ref "U3") (pin "44") (pinfunction "BOOT0_44") (pintype "input"))
      (node (ref "U3") (pin "47") (pinfunction "VSS_3_47") (pintype "input"))
      (node (ref "U4") (pin "2") (pinfunction "GND_2") (pintype "input"))
      (node (ref "Y1") (pin "2") (pinfunction "NC_2") (pintype "input"))
      (node (ref "Y1") (pin "4") (pinfunction "NC_4") (pintype "input"))
    )
    (net (code "29") (name "Net-(C5-Pad2)") (class "Default")
      (node (ref "C5") (pin "2") (pinfunction "2_2") (pintype "input"))
      (node (ref "R4") (pin "1") (pinfunction "1_1") (pintype "input"))
    )
    (net (code "30") (name "Net-(C28-Pad1)") (class "Default")
      (node (ref "C28") (pin "1") (pinfunction "1_1") (pintype "input"))
      (node (ref "C30") (pin "1") (pinfunction "1_1") (pintype "input"))
      (node (ref "C31") (pin "1") (pinfunction "1_1") (pintype "input"))
      (node (ref "C32") (pin "1") (pinfunction "1_1") (pintype "input"))
      (node (ref "C35") (pin "2") (pinfunction "2_2") (pintype "input"))
      (node (ref "C36") (pin "2") (pinfunction "2_2") (pintype "input"))
      (node (ref "C37") (pin "2") (pinfunction "2_2") (pintype "input"))
      (node (ref "C38") (pin "2") (pinfunction "2_2") (pintype "input"))
      (node (ref "C39") (pin "2") (pinfunction "2_2") (pintype "input"))
      (node (ref "L3") (pin "2") (pinfunction "2_2") (pintype "input"))
    )
    (net (code "31") (name "Net-(C28-Pad2)") (class "Default")
      (node (ref "C28") (pin "2") (pinfunction "2_2") (pintype "input"))
      (node (ref "C30") (pin "2") (pinfunction "2_2") (pintype "input"))
      (node (ref "C31") (pin "2") (pinfunction "2_2") (pintype "input"))
      (node (ref "C32") (pin "2") (pinfunction "2_2") (pintype "input"))
      (node (ref "P6") (pin "1") (pinfunction "1_1") (pintype "input"))
    )
    (net (code "32") (name "Net-(D2-A)") (class "Default")
      (node (ref "D2") (pin "7") (pinfunction "A_7") (pintype "input"))
      (node (ref "R19") (pin "2") (pinfunction "2_2") (pintype "input"))
    )
    (net (code "33") (name "Net-(D2-B)") (class "Default")
      (node (ref "D2") (pin "8") (pinfunction "B_8") (pintype "input"))
      (node (ref "R20") (pin "2") (pinfunction "2_2") (pintype "input"))
    )
    (net (code "34") (name "Net-(D2-C)") (class "Default")
      (node (ref "D2") (pin "3") (pinfunction "C_3") (pintype "input"))
      (node (ref "R21") (pin "2") (pinfunction "2_2") (pintype "input"))
    )
    (net (code "35") (name "Net-(D2-D)") (class "Default")
      (node (ref "D2") (pin "2") (pinfunction "D_2") (pintype "input"))
      (node (ref "R22") (pin "2") (pinfunction "2_2") (pintype "input"))
    )
    (net (code "36") (name "Net-(D2-DIG1)") (class "Default")
      (node (ref "D2") (pin "9") (pinfunction "DIG1_9") (pintype "input"))
      (node (ref "Q2") (pin "3") (pinfunction "C_3") (pintype "input"))
    )
    (net (code "37") (name "Net-(D2-DIG2)") (class "Default")
      (node (ref "D2") (pin "6") (pinfunction "DIG2_6") (pintype "input"))
      (node (ref "Q3") (pin "3") (pinfunction "C_3") (pintype "input"))
    )
    (net (code "38") (name "Net-(D2-DP)") (class "Default")
      (node (ref "D2") (pin "5") (pinfunction "DP_5") (pintype "input"))
      (node (ref "R26") (pin "2") (pinfunction "2_2") (pintype "input"))
    )
    (net (code "39") (name "Net-(D2-E)") (class "Default")
      (node (ref "D2") (pin "1") (pinfunction "E_1") (pintype "input"))
      (node (ref "R23") (pin "2") (pinfunction "2_2") (pintype "input"))
    )
    (net (code "40") (name "Net-(D2-F)") (class "Default")
      (node (ref "D2") (pin "10") (pinfunction "F_10") (pintype "input"))
      (node (ref "R24") (pin "2") (pinfunction "2_2") (pintype "input"))
    )
    (net (code "41") (name "Net-(D2-G)") (class "Default")
      (node (ref "D2") (pin "4") (pinfunction "G_4") (pintype "input"))
      (node (ref "R25") (pin "2") (pinfunction "2_2") (pintype "input"))
    )
    (net (code "42") (name "Net-(D5-PadK)") (class "Default")
      (node (ref "D5") (pin "K") (pinfunction "K_K") (pintype "input"))
      (node (ref "R29") (pin "1") (pinfunction "1_1") (pintype "input"))
    )
    (net (code "43") (name "Net-(ON/OFF1-Pad2)") (class "Default")
      (node (ref "ON/OFF1") (pin "2") (pinfunction "2_2") (pintype "input"))
      (node (ref "R10") (pin "2") (pinfunction "2_2") (pintype "input"))
      (node (ref "R9") (pin "2") (pinfunction "2_2") (pintype "input"))
    )
    (net (code "44") (name "Net-(P2-Pad1)") (class "Default")
      (node (ref "P2") (pin "1") (pinfunction "1_1") (pintype "input"))
      (node (ref "R40") (pin "2") (pinfunction "2_2") (pintype "input"))
      (node (ref "R41") (pin "2") (pinfunction "2_2") (pintype "input"))
    )
    (net (code "45") (name "Net-(PWR1-A)") (class "Default")
      (node (ref "PWR1") (pin "1") (pinfunction "A_1") (pintype "input"))
      (node (ref "R5") (pin "2") (pinfunction "2_2") (pintype "input"))
    )
    (net (code "46") (name "Net-(Q1-D)") (class "Default")
      (node (ref "P3") (pin "2") (pinfunction "2_2") (pintype "input"))
      (node (ref "Q1") (pin "3") (pinfunction "D_3") (pintype "input"))
    )
    (net (code "47") (name "Net-(Q1-G)") (class "Default")
      (node (ref "Q1") (pin "1") (pinfunction "G_1") (pintype "input"))
      (node (ref "R12") (pin "2") (pinfunction "2_2") (pintype "input"))
      (node (ref "R13") (pin "1") (pinfunction "1_1") (pintype "input"))
    )
    (net (code "48") (name "Net-(Q2-B)") (class "Default")
      (node (ref "Q2") (pin "1") (pinfunction "B_1") (pintype "input"))
      (node (ref "R14") (pin "1") (pinfunction "1_1") (pintype "input"))
    )
    (net (code "49") (name "Net-(Q3-B)") (class "Default")
      (node (ref "Q3") (pin "1") (pinfunction "B_1") (pintype "input"))
      (node (ref "R15") (pin "1") (pinfunction "1_1") (pintype "input"))
    )
    (net (code "50") (name "Net-(Q4-G)") (class "Default")
      (node (ref "D6") (pin "K") (pinfunction "K_K") (pintype "input"))
      (node (ref "Q4") (pin "1") (pinfunction "G_1") (pintype "input"))
      (node (ref "R33") (pin "2") (pinfunction "2_2") (pintype "input"))
      (node (ref "R34") (pin "1") (pinfunction "1_1") (pintype "input"))
    )
    (net (code "51") (name "Net-(Q5-G)") (class "Default")
      (node (ref "D11") (pin "K") (pinfunction "K_K") (pintype "input"))
      (node (ref "Q5") (pin "1") (pinfunction "G_1") (pintype "input"))
      (node (ref "R38") (pin "2") (pinfunction "2_2") (pintype "input"))
      (node (ref "R39") (pin "1") (pinfunction "1_1") (pintype "input"))
    )
    (net (code "52") (name "Net-(Q6-G)") (class "Default")
      (node (ref "D7") (pin "K") (pinfunction "K_K") (pintype "input"))
      (node (ref "Q6") (pin "1") (pinfunction "G_1") (pintype "input"))
      (node (ref "R42") (pin "1") (pinfunction "1_1") (pintype "input"))
      (node (ref "R43") (pin "2") (pinfunction "2_2") (pintype "input"))
    )
    (net (code "53") (name "Net-(Q7-G)") (class "Default")
      (node (ref "D12") (pin "K") (pinfunction "K_K") (pintype "input"))
      (node (ref "Q7") (pin "1") (pinfunction "G_1") (pintype "input"))
      (node (ref "R47") (pin "1") (pinfunction "1_1") (pintype "input"))
      (node (ref "R48") (pin "2") (pinfunction "2_2") (pintype "input"))
    )
    (net (code "54") (name "Net-(R6-Pad2)") (class "Default")
      (node (ref "R6") (pin "2") (pinfunction "2_2") (pintype "input"))
      (node (ref "R7") (pin "2") (pinfunction "2_2") (pintype "input"))
    )
    (net (code "55") (name "Net-(STA1-A)") (class "Default")
      (node (ref "R11") (pin "2") (pinfunction "2_2") (pintype "input"))
      (node (ref "STA1") (pin "1") (pinfunction "A_1") (pintype "input"))
    )
    (net (code "56") (name "Net-(U1-BOOT)") (class "Default")
      (node (ref "C1") (pin "1") (pinfunction "1_1") (pintype "input"))
      (node (ref "U1") (pin "1") (pinfunction "BOOT_1") (pintype "input"))
    )
    (net (code "57") (name "Net-(U1-COMP)") (class "Default")
      (node (ref "R4") (pin "2") (pinfunction "2_2") (pintype "input"))
      (node (ref "U1") (pin "6") (pinfunction "COMP_6") (pintype "input"))
    )
    (net (code "58") (name "Net-(U1-EN)") (class "Default")
      (node (ref "C6") (pin "1") (pinfunction "1_1") (pintype "input"))
      (node (ref "C7") (pin "2") (pinfunction "2_2") (pintype "input"))
      (node (ref "C8") (pin "2") (pinfunction "2_2") (pintype "input"))
      (node (ref "D1") (pin "K") (pinfunction "K_K") (pintype "input"))
      (node (ref "U1") (pin "2") (pinfunction "VIN_2") (pintype "input"))
      (node (ref "U1") (pin "3") (pinfunction "EN_3") (pintype "input"))
    )
    (net (code "59") (name "Net-(U1-FB)") (class "Default")
      (node (ref "R1") (pin "2") (pinfunction "2_2") (pintype "input"))
      (node (ref "R2") (pin "1") (pinfunction "1_1") (pintype "input"))
      (node (ref "U1") (pin "5") (pinfunction "FB_5") (pintype "input"))
    )
    (net (code "60") (name "Net-(U1-RT{slash}CLK)") (class "Default")
      (node (ref "R3") (pin "2") (pinfunction "2_2") (pintype "input"))
      (node (ref "U1") (pin "4") (pinfunction "RT/CLK_4") (pintype "input"))
    )
    (net (code "61") (name "Net-(U1-SW)") (class "Default")
      (node (ref "C1") (pin "2") (pinfunction "2_2") (pintype "input"))
      (node (ref "L1") (pin "1") (pinfunction "1_1") (pintype "input"))
      (node (ref "U1") (pin "8") (pinfunction "SW_8") (pintype "input"))
    )
    (net (code "62") (name "Net-(U2-BS)") (class "Default")
      (node (ref "C14") (pin "1") (pinfunction "1_1") (pintype "input"))
      (node (ref "U2") (pin "1") (pinfunction "BS_1") (pintype "input"))
    )
    (net (code "63") (name "Net-(U2-FB)") (class "Default")
      (node (ref "C13") (pin "2") (pinfunction "2_2") (pintype "input"))
      (node (ref "R7") (pin "1") (pinfunction "1_1") (pintype "input"))
      (node (ref "R8") (pin "1") (pinfunction "1_1") (pintype "input"))
      (node (ref "U2") (pin "3") (pinfunction "FB_3") (pintype "input"))
    )
    (net (code "64") (name "Net-(U2-SW)") (class "Default")
      (node (ref "C14") (pin "2") (pinfunction "2_2") (pintype "input"))
      (node (ref "L2") (pin "2") (pinfunction "2_2") (pintype "input"))
      (node (ref "U2") (pin "6") (pinfunction "SW_6") (pintype "input"))
    )
    (net (code "65") (name "Net-(U3-OSC_IN{slash}PD0)") (class "Default")
      (node (ref "C17") (pin "1") (pinfunction "1_1") (pintype "input"))
      (node (ref "U3") (pin "5") (pinfunction "OSC_IN/PD0_5") (pintype "input"))
      (node (ref "Y1") (pin "1") (pinfunction "OSC1_1") (pintype "input"))
    )
    (net (code "66") (name "Net-(U3-OSC_OUT{slash}PD1)") (class "Default")
      (node (ref "C18") (pin "1") (pinfunction "1_1") (pintype "input"))
      (node (ref "U3") (pin "6") (pinfunction "OSC_OUT/PD1_6") (pintype "input"))
      (node (ref "Y1") (pin "3") (pinfunction "OSC2_3") (pintype "input"))
    )
    (net (code "67") (name "Net-(U3-VDDA)") (class "Default")
      (node (ref "C44") (pin "1") (pinfunction "1_1") (pintype "input"))
      (node (ref "FB2") (pin "2") (pinfunction "2_2") (pintype "input"))
      (node (ref "U3") (pin "9") (pinfunction "VDDA_9") (pintype "input"))
    )
    (net (code "68") (name "Net-(U3-VSSA)") (class "Default")
      (node (ref "C44") (pin "2") (pinfunction "2_2") (pintype "input"))
      (node (ref "FB3") (pin "1") (pinfunction "1_1") (pintype "input"))
      (node (ref "U3") (pin "8") (pinfunction "VSSA_8") (pintype "input"))
    )
    (net (code "69") (name "Net-(U4-OUT)") (class "Default")
      (node (ref "R31") (pin "1") (pinfunction "1_1") (pintype "input"))
      (node (ref "U4") (pin "6") (pinfunction "OUT_6") (pintype "input"))
    )
    (net (code "70") (name "Net-(U4-REF)") (class "Default")
      (node (ref "R27") (pin "1") (pinfunction "1_1") (pintype "input"))
      (node (ref "R28") (pin "1") (pinfunction "1_1") (pintype "input"))
      (node (ref "U4") (pin "1") (pinfunction "REF_1") (pintype "input"))
    )
    (net (code "71") (name "Net-(U5-DT)") (class "Default")
      (node (ref "R49") (pin "1") (pinfunction "1_1") (pintype "input"))
      (node (ref "U5") (pin "6") (pinfunction "DT_6") (pintype "input"))
    )
    (net (code "72") (name "Net-(U5-HO)") (class "Default")
      (node (ref "R33") (pin "1") (pinfunction "1_1") (pintype "input"))
      (node (ref "U5") (pin "3") (pinfunction "HO_3") (pintype "input"))
    )
    (net (code "73") (name "Net-(U5-LO)") (class "Default")
      (node (ref "R38") (pin "1") (pinfunction "1_1") (pintype "input"))
      (node (ref "U5") (pin "10") (pinfunction "LO_10") (pintype "input"))
    )
    (net (code "74") (name "Net-(U5-VB)") (class "Default")
      (node (ref "C29") (pin "1") (pinfunction "1_1") (pintype "input"))
      (node (ref "D4") (pin "K") (pinfunction "K_K") (pintype "input"))
      (node (ref "D9") (pin "K") (pinfunction "K_K") (pintype "input"))
      (node (ref "U5") (pin "2") (pinfunction "VB_2") (pintype "input"))
    )
    (net (code "75") (name "Net-(U5-VS)") (class "Default")
      (node (ref "C29") (pin "2") (pinfunction "2_2") (pintype "input"))
      (node (ref "D9") (pin "A") (pinfunction "A_A") (pintype "input"))
      (node (ref "R37") (pin "1") (pinfunction "1_1") (pintype "input"))
      (node (ref "U5") (pin "4") (pinfunction "VS_4") (pintype "input"))
    )
    (net (code "76") (name "Net-(U6-DT)") (class "Default")
      (node (ref "R50") (pin "2") (pinfunction "2_2") (pintype "input"))
      (node (ref "U6") (pin "6") (pinfunction "DT_6") (pintype "input"))
    )
    (net (code "77") (name "Net-(U6-HO)") (class "Default")
      (node (ref "R42") (pin "2") (pinfunction "2_2") (pintype "input"))
      (node (ref "U6") (pin "3") (pinfunction "HO_3") (pintype "input"))
    )
    (net (code "78") (name "Net-(U6-LO)") (class "Default")
      (node (ref "R47") (pin "2") (pinfunction "2_2") (pintype "input"))
      (node (ref "U6") (pin "10") (pinfunction "LO_10") (pintype "input"))
    )
    (net (code "79") (name "Net-(U6-VB)") (class "Default")
      (node (ref "C34") (pin "2") (pinfunction "2_2") (pintype "input"))
      (node (ref "D10") (pin "K") (pinfunction "K_K") (pintype "input"))
      (node (ref "D8") (pin "K") (pinfunction "K_K") (pintype "input"))
      (node (ref "U6") (pin "2") (pinfunction "VB_2") (pintype "input"))
    )
    (net (code "80") (name "Net-(U6-VS)") (class "Default")
      (node (ref "C34") (pin "1") (pinfunction "1_1") (pintype "input"))
      (node (ref "D10") (pin "A") (pinfunction "A_A") (pintype "input"))
      (node (ref "R46") (pin "2") (pinfunction "2_2") (pintype "input"))
      (node (ref "U6") (pin "4") (pinfunction "VS_4") (pintype "input"))
    )
    (net (code "81") (name "VBAT") (class "Default")
      (node (ref "C10") (pin "1") (pinfunction "1_1") (pintype "input"))
      (node (ref "C9") (pin "1") (pinfunction "1_1") (pintype "input"))
      (node (ref "D1") (pin "A") (pinfunction "A_A") (pintype "input"))
      (node (ref "P1") (pin "2") (pinfunction "2_2") (pintype "input"))
      (node (ref "R32") (pin "1") (pinfunction "1_1") (pintype "input"))
      (node (ref "U4") (pin "4") (pinfunction "IN+_4") (pintype "input"))
    )
    (net (code "82") (name "VBATO") (class "Default")
      (node (ref "C26") (pin "1") (pinfunction "1_1") (pintype "input"))
      (node (ref "C27") (pin "1") (pinfunction "1_1") (pintype "input"))
      (node (ref "C41") (pin "2") (pinfunction "2_2") (pintype "input"))
      (node (ref "C42") (pin "2") (pinfunction "2_2") (pintype "input"))
      (node (ref "D5") (pin "A") (pinfunction "A_A") (pintype "input"))
      (node (ref "Q4") (pin "2") (pinfunction "D_2") (pintype "input"))
      (node (ref "Q6") (pin "2") (pinfunction "D_2") (pintype "input"))
      (node (ref "R32") (pin "2") (pinfunction "2_2") (pintype "input"))
      (node (ref "U4") (pin "5") (pinfunction "IN-_5") (pintype "input"))
    )
    (net (code "83") (name "VCC3V3") (class "Default")
      (node (ref "C11") (pin "1") (pinfunction "1_1") (pintype "input"))
      (node (ref "C12") (pin "1") (pinfunction "1_1") (pintype "input"))
      (node (ref "C13") (pin "1") (pinfunction "1_1") (pintype "input"))
      (node (ref "C20") (pin "2") (pinfunction "2_2") (pintype "input"))
      (node (ref "C21") (pin "2") (pinfunction "2_2") (pintype "input"))
      (node (ref "C22") (pin "2") (pinfunction "2_2") (pintype "input"))
      (node (ref "C23") (pin "2") (pinfunction "2_2") (pintype "input"))
      (node (ref "FB2") (pin "1") (pinfunction "1_1") (pintype "input"))
      (node (ref "L2") (pin "1") (pinfunction "1_1") (pintype "input"))
      (node (ref "P4") (pin "1") (pinfunction "3V3_1") (pintype "input"))
      (node (ref "P5") (pin "3") (pinfunction "3_3") (pintype "input"))
      (node (ref "Q2") (pin "2") (pinfunction "E_2") (pintype "input"))
      (node (ref "Q3") (pin "2") (pinfunction "E_2") (pintype "input"))
      (node (ref "R11") (pin "1") (pinfunction "1_1") (pintype "input"))
      (node (ref "R18") (pin "1") (pinfunction "1_1") (pintype "input"))
      (node (ref "R28") (pin "2") (pinfunction "2_2") (pintype "input"))
      (node (ref "R5") (pin "1") (pinfunction "1_1") (pintype "input"))
      (node (ref "R6") (pin "1") (pinfunction "1_1") (pintype "input"))
      (node (ref "R9") (pin "1") (pinfunction "1_1") (pintype "input"))
      (node (ref "U3") (pin "1") (pinfunction "VBAT_1") (pintype "input"))
      (node (ref "U3") (pin "24") (pinfunction "VDD_VIO_1_24") (pintype "input"))
      (node (ref "U3") (pin "36") (pinfunction "VDD_2_36") (pintype "input"))
      (node (ref "U3") (pin "48") (pinfunction "VDD_VIO_3_48") (pintype "input"))
      (node (ref "U4") (pin "3") (pinfunction "V+_3") (pintype "input"))
    )
    (net (code "84") (name "VCC12V") (class "Default")
      (node (ref "C15") (pin "1") (pinfunction "1_1") (pintype "input"))
      (node (ref "C16") (pin "1") (pinfunction "1_1") (pintype "input"))
      (node (ref "C2") (pin "2") (pinfunction "2_2") (pintype "input"))
      (node (ref "C3") (pin "1") (pinfunction "1_1") (pintype "input"))
      (node (ref "C33") (pin "1") (pinfunction "1_1") (pintype "input"))
      (node (ref "C4") (pin "2") (pinfunction "2_2") (pintype "input"))
      (node (ref "C40") (pin "2") (pinfunction "2_2") (pintype "input"))
      (node (ref "D4") (pin "A") (pinfunction "A_A") (pintype "input"))
      (node (ref "D8") (pin "A") (pinfunction "A_A") (pintype "input"))
      (node (ref "L1") (pin "2") (pinfunction "2_2") (pintype "input"))
      (node (ref "P3") (pin "1") (pinfunction "1_1") (pintype "input"))
      (node (ref "P5") (pin "2") (pinfunction "2_2") (pintype "input"))
      (node (ref "R1") (pin "1") (pinfunction "1_1") (pintype "input"))
      (node (ref "U2") (pin "4") (pinfunction "EN_4") (pintype "input"))
      (node (ref "U2") (pin "5") (pinfunction "IN_5") (pintype "input"))
      (node (ref "U5") (pin "1") (pinfunction "VCC_1") (pintype "input"))
      (node (ref "U6") (pin "1") (pinfunction "VCC_1") (pintype "input"))
    )
    (net (code "85") (name "unconnected-(M1-Pad1)") (class "Default")
      (node (ref "M1") (pin "1") (pinfunction "1_1") (pintype "input+no_connect"))
    )
    (net (code "86") (name "unconnected-(M2-Pad1)") (class "Default")
      (node (ref "M2") (pin "1") (pinfunction "1_1") (pintype "input+no_connect"))
    )
    (net (code "87") (name "unconnected-(M3-Pad1)") (class "Default")
      (node (ref "M3") (pin "1") (pinfunction "1_1") (pintype "input+no_connect"))
    )
    (net (code "88") (name "unconnected-(M4-Pad1)") (class "Default")
      (node (ref "M4") (pin "1") (pinfunction "1_1") (pintype "input+no_connect"))
    )
    (net (code "89") (name "unconnected-(M5-Pad1)") (class "Default")
      (node (ref "M5") (pin "1") (pinfunction "1_1") (pintype "input+no_connect"))
    )
    (net (code "90") (name "unconnected-(M6-Pad1)") (class "Default")
      (node (ref "M6") (pin "1") (pinfunction "1_1") (pintype "input+no_connect"))
    )
    (net (code "91") (name "unconnected-(P4-NC-Pad6)") (class "Default")
      (node (ref "P4") (pin "6") (pinfunction "NC_6") (pintype "input+no_connect"))
    )
    (net (code "92") (name "unconnected-(P4-NC-Pad8)") (class "Default")
      (node (ref "P4") (pin "8") (pinfunction "NC_8") (pintype "input+no_connect"))
    )
    (net (code "93") (name "unconnected-(U3-PA11{slash}USB1DM-Pad32)") (class "Default")
      (node (ref "U3") (pin "32") (pinfunction "PA11/USB1DM_32") (pintype "input+no_connect"))
    )
    (net (code "94") (name "unconnected-(U3-PA12{slash}USB1DP-Pad33)") (class "Default")
      (node (ref "U3") (pin "33") (pinfunction "PA12/USB1DP_33") (pintype "input+no_connect"))
    )
    (net (code "95") (name "unconnected-(U3-PB9-Pad46)") (class "Default")
      (node (ref "U3") (pin "46") (pinfunction "PB9_46") (pintype "input+no_connect"))
    )
    (net (code "96") (name "unconnected-(U3-PB10-Pad21)") (class "Default")
      (node (ref "U3") (pin "21") (pinfunction "PB10_21") (pintype "input+no_connect"))
    )
    (net (code "97") (name "unconnected-(U3-PB11-Pad22)") (class "Default")
      (node (ref "U3") (pin "22") (pinfunction "PB11_22") (pintype "input+no_connect"))
    )
    (net (code "98") (name "unconnected-(U3-PB12-Pad25)") (class "Default")
      (node (ref "U3") (pin "25") (pinfunction "PB12_25") (pintype "input+no_connect"))
    )
    (net (code "99") (name "unconnected-(U3-PB13-Pad26)") (class "Default")
      (node (ref "U3") (pin "26") (pinfunction "PB13_26") (pintype "input+no_connect"))
    )
    (net (code "100") (name "unconnected-(U3-PB14-Pad27)") (class "Default")
      (node (ref "U3") (pin "27") (pinfunction "PB14_27") (pintype "input+no_connect"))
    )
    (net (code "101") (name "unconnected-(U3-PB15-Pad28)") (class "Default")
      (node (ref "U3") (pin "28") (pinfunction "PB15_28") (pintype "input+no_connect"))
    )
    (net (code "102") (name "unconnected-(U3-PC13{slash}TAMPER_RTC-Pad2)") (class "Default")
      (node (ref "U3") (pin "2") (pinfunction "PC13/TAMPER_RTC_2") (pintype "input+no_connect"))
    )
    (net (code "103") (name "unconnected-(U3-PC14{slash}OSC32IN-Pad3)") (class "Default")
      (node (ref "U3") (pin "3") (pinfunction "PC14/OSC32IN_3") (pintype "input+no_connect"))
    )
    (net (code "104") (name "unconnected-(U3-PC15{slash}OSC32OUT-Pad4)") (class "Default")
      (node (ref "U3") (pin "4") (pinfunction "PC15/OSC32OUT_4") (pintype "input+no_connect"))
    )
    (net (code "105") (name "unconnected-(U5-NC-Pad5)") (class "Default")
      (node (ref "U5") (pin "5") (pinfunction "NC_5") (pintype "input+no_connect"))
    )
    (net (code "106") (name "unconnected-(U6-NC-Pad5)") (class "Default")
      (node (ref "U6") (pin "5") (pinfunction "NC_5") (pintype "input+no_connect"))
    )
  )
)
